# nola7a.net
KiCad netlist of a schematic drawn in EAGLE
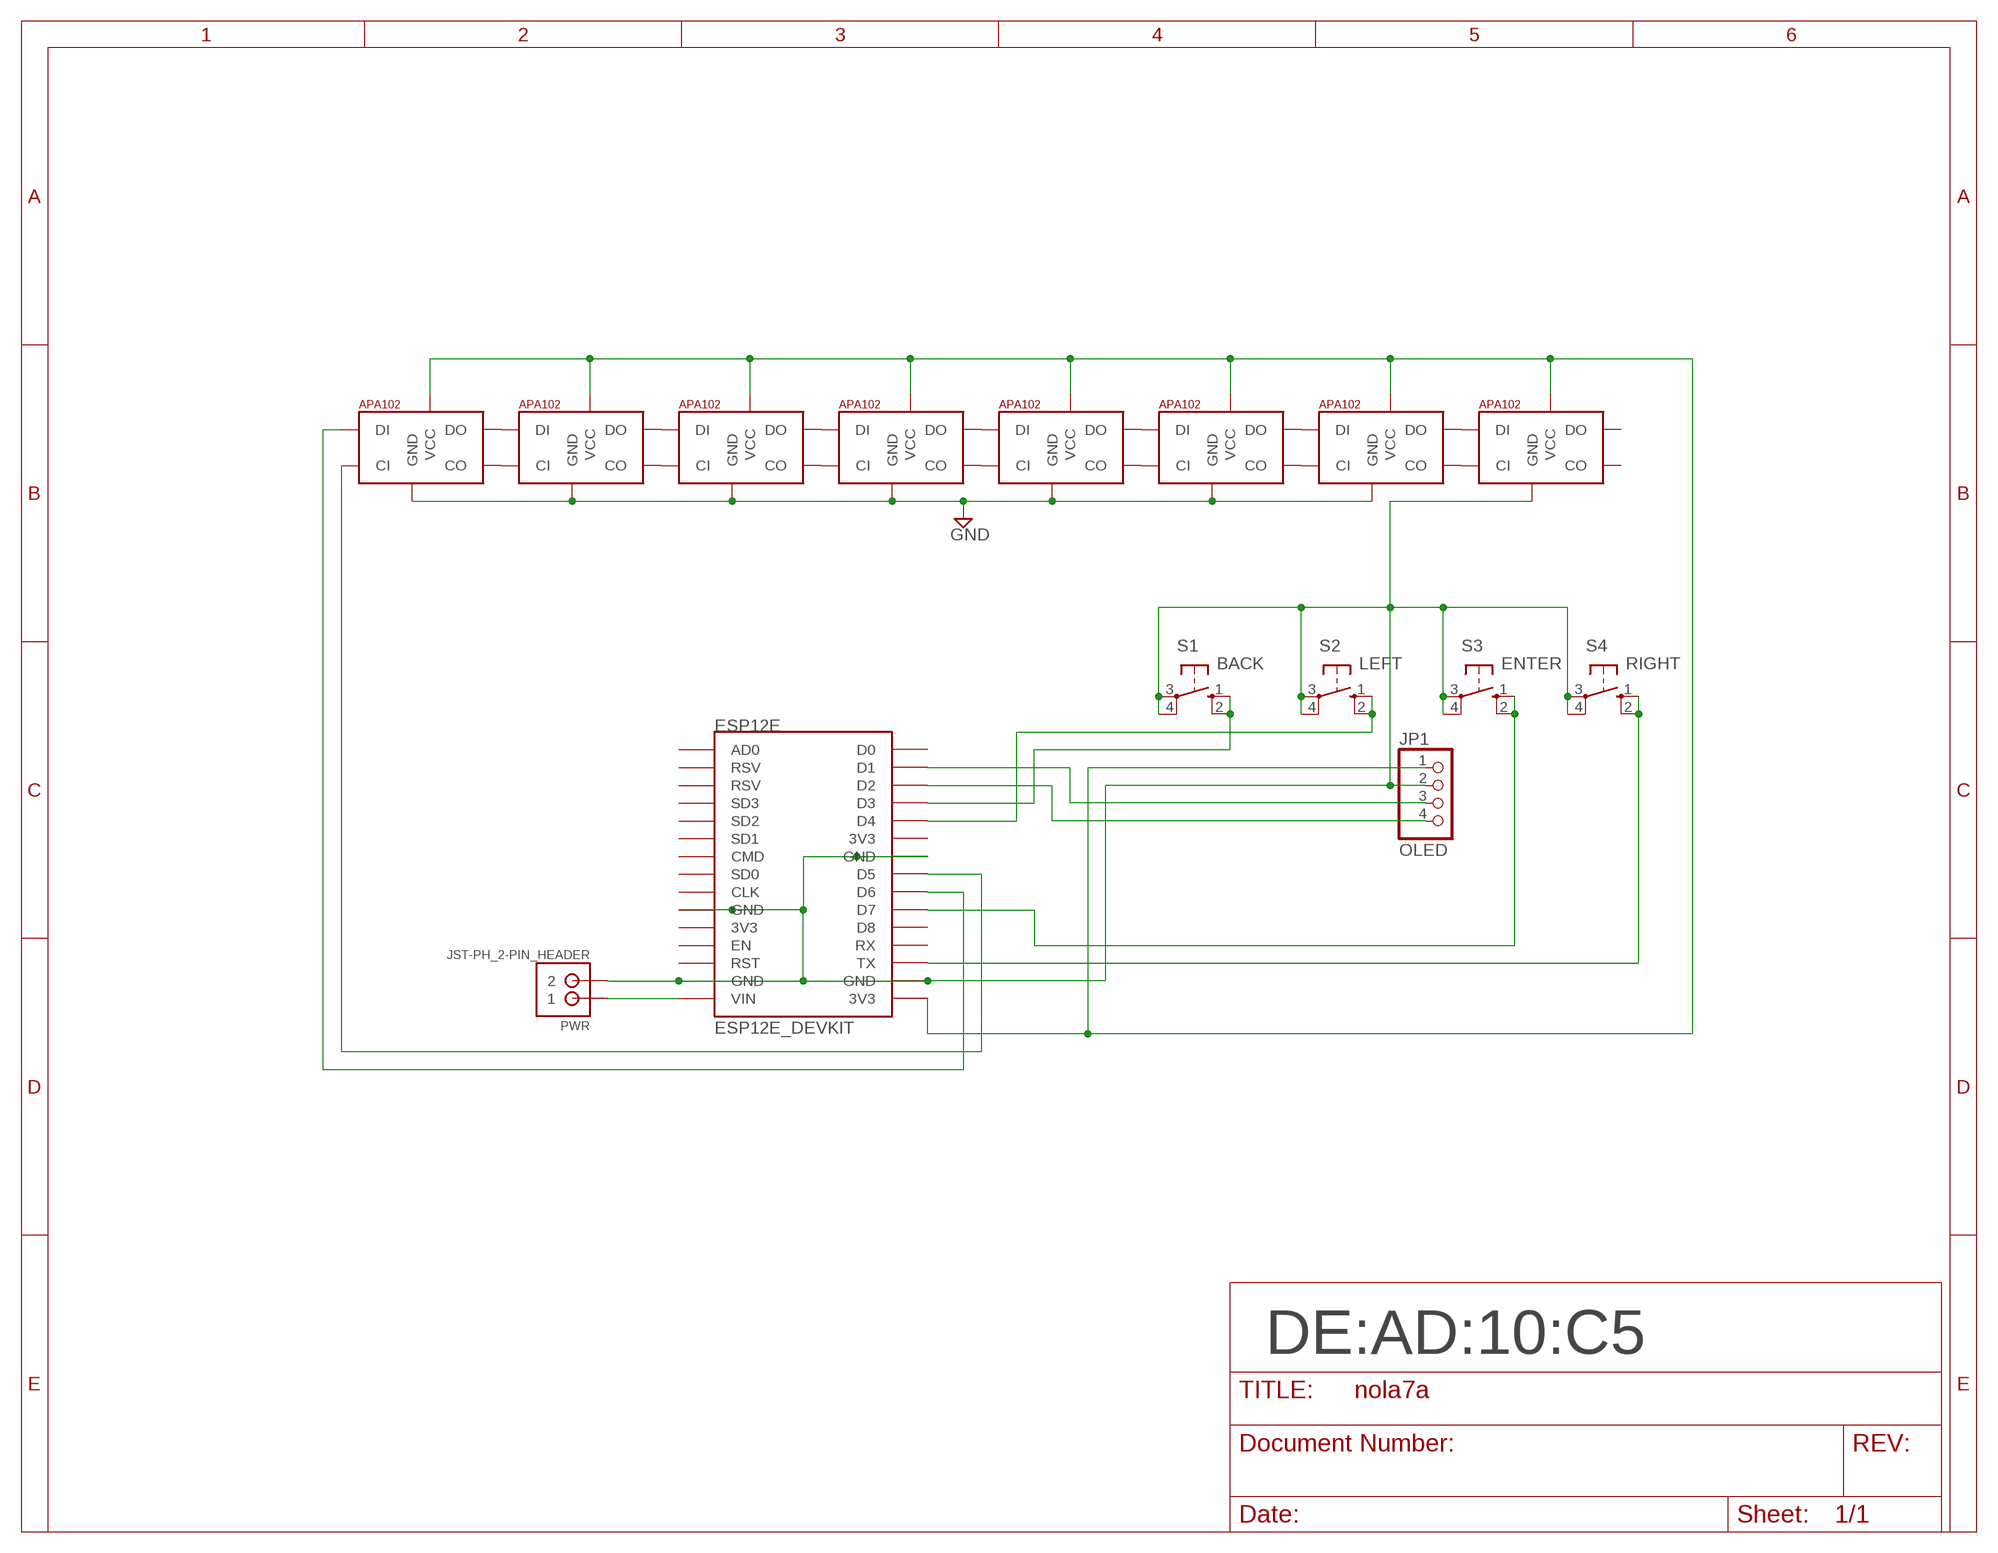
[diagram p0: schematic, sheet 1]

(export (version "E")
  (design (tool "Eeschema 10.0.6"))
  (components
    (comp (ref "ESP12E")
      (value "ESP12E_DEVKIT")
      (footprint "eagle-import:ESP12E_DEVKIT")
      (libsource (lib "eagle-import") (part "ESP12E_DEVKIT"))
    )
    (comp (ref "JP1")
      (value "OLED")
      (footprint "eagle-import:1X04")
      (libsource (lib "eagle-import") (part "PINHD-1X4"))
    )
    (comp (ref "LED1")
      (value "APA1025050")
      (footprint "eagle-import:APA102_5050")
      (libsource (lib "eagle-import") (part "APA1025050"))
    )
    (comp (ref "LED2")
      (value "APA1025050")
      (footprint "eagle-import:APA102_5050")
      (libsource (lib "eagle-import") (part "APA1025050"))
    )
    (comp (ref "LED3")
      (value "APA1025050")
      (footprint "eagle-import:APA102_5050")
      (libsource (lib "eagle-import") (part "APA1025050"))
    )
    (comp (ref "LED4")
      (value "APA1025050")
      (footprint "eagle-import:APA102_5050")
      (libsource (lib "eagle-import") (part "APA1025050"))
    )
    (comp (ref "LED5")
      (value "APA1025050")
      (footprint "eagle-import:APA102_5050")
      (libsource (lib "eagle-import") (part "APA1025050"))
    )
    (comp (ref "LED6")
      (value "APA1025050")
      (footprint "eagle-import:APA102_5050")
      (libsource (lib "eagle-import") (part "APA1025050"))
    )
    (comp (ref "LED7")
      (value "APA1025050")
      (footprint "eagle-import:APA102_5050")
      (libsource (lib "eagle-import") (part "APA1025050"))
    )
    (comp (ref "LED8")
      (value "APA1025050")
      (footprint "eagle-import:APA102_5050")
      (libsource (lib "eagle-import") (part "APA1025050"))
    )
    (comp (ref "PWR")
      (value "JST-PH_2-PIN_HEADER")
      (footprint "eagle-import:JST_B2B-PH_HEADER")
      (libsource (lib "eagle-import") (part "JST-PH_2-PIN_HEADER"))
    )
    (comp (ref "S1")
      (value "BACK")
      (footprint "eagle-import:B3F-10XX")
      (fields (field (name "MPN") "B3F-1000"))
      (libsource (lib "eagle-import") (part "10-XX"))
    )
    (comp (ref "S2")
      (value "LEFT")
      (footprint "eagle-import:B3F-10XX")
      (fields (field (name "MPN") "B3F-1000"))
      (libsource (lib "eagle-import") (part "10-XX"))
    )
    (comp (ref "S3")
      (value "ENTER")
      (footprint "eagle-import:B3F-10XX")
      (fields (field (name "MPN") "B3F-1000"))
      (libsource (lib "eagle-import") (part "10-XX"))
    )
    (comp (ref "S4")
      (value "RIGHT")
      (footprint "eagle-import:B3F-10XX")
      (fields (field (name "MPN") "B3F-1000"))
      (libsource (lib "eagle-import") (part "10-XX"))
    )
  )
  (nets
    (net (code "1") (name "GND") (class "Default")
      (node (ref "ESP12E") (pin "GND@0") (pinfunction "GND_GND@0") (pintype "bidirectional"))
      (node (ref "ESP12E") (pin "GND@1") (pinfunction "GND_GND@1") (pintype "bidirectional"))
      (node (ref "ESP12E") (pin "GND@2") (pinfunction "GND_GND@2") (pintype "bidirectional"))
      (node (ref "ESP12E") (pin "GND@3") (pinfunction "GND_GND@3") (pintype "bidirectional"))
      (node (ref "JP1") (pin "2") (pinfunction "2_2") (pintype "passive"))
      (node (ref "LED1") (pin "6") (pinfunction "GND_6") (pintype "bidirectional"))
      (node (ref "LED2") (pin "6") (pinfunction "GND_6") (pintype "bidirectional"))
      (node (ref "LED3") (pin "6") (pinfunction "GND_6") (pintype "bidirectional"))
      (node (ref "LED4") (pin "6") (pinfunction "GND_6") (pintype "bidirectional"))
      (node (ref "LED5") (pin "6") (pinfunction "GND_6") (pintype "bidirectional"))
      (node (ref "LED6") (pin "6") (pinfunction "GND_6") (pintype "bidirectional"))
      (node (ref "LED7") (pin "6") (pinfunction "GND_6") (pintype "bidirectional"))
      (node (ref "LED8") (pin "6") (pinfunction "GND_6") (pintype "bidirectional"))
      (node (ref "PWR") (pin "P2") (pinfunction "2_P2") (pintype "bidirectional"))
      (node (ref "S1") (pin "3") (pinfunction "P_3") (pintype "passive"))
      (node (ref "S1") (pin "4") (pinfunction "P1_4") (pintype "passive"))
      (node (ref "S2") (pin "3") (pinfunction "P_3") (pintype "passive"))
      (node (ref "S2") (pin "4") (pinfunction "P1_4") (pintype "passive"))
      (node (ref "S3") (pin "3") (pinfunction "P_3") (pintype "passive"))
      (node (ref "S3") (pin "4") (pinfunction "P1_4") (pintype "passive"))
      (node (ref "S4") (pin "3") (pinfunction "P_3") (pintype "passive"))
      (node (ref "S4") (pin "4") (pinfunction "P1_4") (pintype "passive"))
    )
    (net (code "2") (name "Net-(ESP12E-PadD1)") (class "Default")
      (node (ref "ESP12E") (pin "D1") (pinfunction "D1_D1") (pintype "bidirectional"))
      (node (ref "JP1") (pin "3") (pinfunction "3_3") (pintype "passive"))
    )
    (net (code "3") (name "Net-(ESP12E-PadD2)") (class "Default")
      (node (ref "ESP12E") (pin "D2") (pinfunction "D2_D2") (pintype "bidirectional"))
      (node (ref "JP1") (pin "4") (pinfunction "4_4") (pintype "passive"))
    )
    (net (code "4") (name "Net-(LED1-CI)") (class "Default")
      (node (ref "ESP12E") (pin "D5") (pinfunction "D5_D5") (pintype "bidirectional"))
      (node (ref "LED1") (pin "5") (pinfunction "CI_5") (pintype "bidirectional"))
    )
    (net (code "5") (name "Net-(LED1-CO)") (class "Default")
      (node (ref "LED1") (pin "2") (pinfunction "CO_2") (pintype "bidirectional"))
      (node (ref "LED2") (pin "5") (pinfunction "CI_5") (pintype "bidirectional"))
    )
    (net (code "6") (name "Net-(LED1-DI)") (class "Default")
      (node (ref "ESP12E") (pin "D6") (pinfunction "D6_D6") (pintype "bidirectional"))
      (node (ref "LED1") (pin "4") (pinfunction "DI_4") (pintype "bidirectional"))
    )
    (net (code "7") (name "Net-(LED1-DO)") (class "Default")
      (node (ref "LED1") (pin "3") (pinfunction "DO_3") (pintype "bidirectional"))
      (node (ref "LED2") (pin "4") (pinfunction "DI_4") (pintype "bidirectional"))
    )
    (net (code "8") (name "Net-(LED1-VCC)") (class "Default")
      (node (ref "ESP12E") (pin "3V3@2") (pinfunction "3V3_3V3@2") (pintype "bidirectional"))
      (node (ref "JP1") (pin "1") (pinfunction "1_1") (pintype "passive"))
      (node (ref "LED1") (pin "1") (pinfunction "VCC_1") (pintype "bidirectional"))
      (node (ref "LED2") (pin "1") (pinfunction "VCC_1") (pintype "bidirectional"))
      (node (ref "LED3") (pin "1") (pinfunction "VCC_1") (pintype "bidirectional"))
      (node (ref "LED4") (pin "1") (pinfunction "VCC_1") (pintype "bidirectional"))
      (node (ref "LED5") (pin "1") (pinfunction "VCC_1") (pintype "bidirectional"))
      (node (ref "LED6") (pin "1") (pinfunction "VCC_1") (pintype "bidirectional"))
      (node (ref "LED7") (pin "1") (pinfunction "VCC_1") (pintype "bidirectional"))
      (node (ref "LED8") (pin "1") (pinfunction "VCC_1") (pintype "bidirectional"))
    )
    (net (code "9") (name "Net-(LED2-CO)") (class "Default")
      (node (ref "LED2") (pin "2") (pinfunction "CO_2") (pintype "bidirectional"))
      (node (ref "LED3") (pin "5") (pinfunction "CI_5") (pintype "bidirectional"))
    )
    (net (code "10") (name "Net-(LED2-DO)") (class "Default")
      (node (ref "LED2") (pin "3") (pinfunction "DO_3") (pintype "bidirectional"))
      (node (ref "LED3") (pin "4") (pinfunction "DI_4") (pintype "bidirectional"))
    )
    (net (code "11") (name "Net-(LED3-CO)") (class "Default")
      (node (ref "LED3") (pin "2") (pinfunction "CO_2") (pintype "bidirectional"))
      (node (ref "LED4") (pin "5") (pinfunction "CI_5") (pintype "bidirectional"))
    )
    (net (code "12") (name "Net-(LED3-DO)") (class "Default")
      (node (ref "LED3") (pin "3") (pinfunction "DO_3") (pintype "bidirectional"))
      (node (ref "LED4") (pin "4") (pinfunction "DI_4") (pintype "bidirectional"))
    )
    (net (code "13") (name "Net-(LED4-CO)") (class "Default")
      (node (ref "LED4") (pin "2") (pinfunction "CO_2") (pintype "bidirectional"))
      (node (ref "LED5") (pin "5") (pinfunction "CI_5") (pintype "bidirectional"))
    )
    (net (code "14") (name "Net-(LED4-DO)") (class "Default")
      (node (ref "LED4") (pin "3") (pinfunction "DO_3") (pintype "bidirectional"))
      (node (ref "LED5") (pin "4") (pinfunction "DI_4") (pintype "bidirectional"))
    )
    (net (code "15") (name "Net-(LED5-CO)") (class "Default")
      (node (ref "LED5") (pin "2") (pinfunction "CO_2") (pintype "bidirectional"))
      (node (ref "LED6") (pin "5") (pinfunction "CI_5") (pintype "bidirectional"))
    )
    (net (code "16") (name "Net-(LED5-DO)") (class "Default")
      (node (ref "LED5") (pin "3") (pinfunction "DO_3") (pintype "bidirectional"))
      (node (ref "LED6") (pin "4") (pinfunction "DI_4") (pintype "bidirectional"))
    )
    (net (code "17") (name "Net-(LED6-CO)") (class "Default")
      (node (ref "LED6") (pin "2") (pinfunction "CO_2") (pintype "bidirectional"))
      (node (ref "LED7") (pin "5") (pinfunction "CI_5") (pintype "bidirectional"))
    )
    (net (code "18") (name "Net-(LED6-DO)") (class "Default")
      (node (ref "LED6") (pin "3") (pinfunction "DO_3") (pintype "bidirectional"))
      (node (ref "LED7") (pin "4") (pinfunction "DI_4") (pintype "bidirectional"))
    )
    (net (code "19") (name "Net-(LED7-CO)") (class "Default")
      (node (ref "LED7") (pin "2") (pinfunction "CO_2") (pintype "bidirectional"))
      (node (ref "LED8") (pin "5") (pinfunction "CI_5") (pintype "bidirectional"))
    )
    (net (code "20") (name "Net-(LED7-DO)") (class "Default")
      (node (ref "LED7") (pin "3") (pinfunction "DO_3") (pintype "bidirectional"))
      (node (ref "LED8") (pin "4") (pinfunction "DI_4") (pintype "bidirectional"))
    )
    (net (code "21") (name "Net-(PWR-1)") (class "Default")
      (node (ref "ESP12E") (pin "VIN") (pinfunction "VIN_VIN") (pintype "bidirectional"))
      (node (ref "PWR") (pin "P1") (pinfunction "1_P1") (pintype "bidirectional"))
    )
    (net (code "22") (name "Net-(S1-S)") (class "Default")
      (node (ref "ESP12E") (pin "D3") (pinfunction "D3_D3") (pintype "bidirectional"))
      (node (ref "S1") (pin "1") (pinfunction "S_1") (pintype "passive"))
      (node (ref "S1") (pin "2") (pinfunction "S1_2") (pintype "passive"))
    )
    (net (code "23") (name "Net-(S2-S)") (class "Default")
      (node (ref "ESP12E") (pin "D4") (pinfunction "D4_D4") (pintype "bidirectional"))
      (node (ref "S2") (pin "1") (pinfunction "S_1") (pintype "passive"))
      (node (ref "S2") (pin "2") (pinfunction "S1_2") (pintype "passive"))
    )
    (net (code "24") (name "Net-(S3-S)") (class "Default")
      (node (ref "ESP12E") (pin "D7") (pinfunction "D7_D7") (pintype "bidirectional"))
      (node (ref "S3") (pin "1") (pinfunction "S_1") (pintype "passive"))
      (node (ref "S3") (pin "2") (pinfunction "S1_2") (pintype "passive"))
    )
    (net (code "25") (name "Net-(S4-S)") (class "Default")
      (node (ref "ESP12E") (pin "TX") (pinfunction "TX_TX") (pintype "bidirectional"))
      (node (ref "S4") (pin "1") (pinfunction "S_1") (pintype "passive"))
      (node (ref "S4") (pin "2") (pinfunction "S1_2") (pintype "passive"))
    )
    (net (code "26") (name "unconnected-(ESP12E-3V3-Pad3V3@0)") (class "Default")
      (node (ref "ESP12E") (pin "3V3@0") (pinfunction "3V3_3V3@0") (pintype "bidirectional"))
    )
    (net (code "27") (name "unconnected-(ESP12E-3V3-Pad3V3@1)") (class "Default")
      (node (ref "ESP12E") (pin "3V3@1") (pinfunction "3V3_3V3@1") (pintype "bidirectional"))
    )
    (net (code "28") (name "unconnected-(ESP12E-PadAD0)") (class "Default")
      (node (ref "ESP12E") (pin "AD0") (pinfunction "AD0_AD0") (pintype "bidirectional"))
    )
    (net (code "29") (name "unconnected-(ESP12E-PadCLK)") (class "Default")
      (node (ref "ESP12E") (pin "CLK") (pinfunction "CLK_CLK") (pintype "bidirectional"))
    )
    (net (code "30") (name "unconnected-(ESP12E-PadCMD)") (class "Default")
      (node (ref "ESP12E") (pin "CMD") (pinfunction "CMD_CMD") (pintype "bidirectional"))
    )
    (net (code "31") (name "unconnected-(ESP12E-PadD0)") (class "Default")
      (node (ref "ESP12E") (pin "D0") (pinfunction "D0_D0") (pintype "bidirectional"))
    )
    (net (code "32") (name "unconnected-(ESP12E-PadD8)") (class "Default")
      (node (ref "ESP12E") (pin "D8") (pinfunction "D8_D8") (pintype "bidirectional"))
    )
    (net (code "33") (name "unconnected-(ESP12E-PadEN)") (class "Default")
      (node (ref "ESP12E") (pin "EN") (pinfunction "EN_EN") (pintype "bidirectional"))
    )
    (net (code "34") (name "unconnected-(ESP12E-PadRST)") (class "Default")
      (node (ref "ESP12E") (pin "RST") (pinfunction "RST_RST") (pintype "bidirectional"))
    )
    (net (code "35") (name "unconnected-(ESP12E-PadRX)") (class "Default")
      (node (ref "ESP12E") (pin "RX") (pinfunction "RX_RX") (pintype "bidirectional"))
    )
    (net (code "36") (name "unconnected-(ESP12E-PadSD0)") (class "Default")
      (node (ref "ESP12E") (pin "SD0") (pinfunction "SD0_SD0") (pintype "bidirectional"))
    )
    (net (code "37") (name "unconnected-(ESP12E-PadSD1)") (class "Default")
      (node (ref "ESP12E") (pin "SD1") (pinfunction "SD1_SD1") (pintype "bidirectional"))
    )
    (net (code "38") (name "unconnected-(ESP12E-PadSD2)") (class "Default")
      (node (ref "ESP12E") (pin "SD2") (pinfunction "SD2_SD2") (pintype "bidirectional"))
    )
    (net (code "39") (name "unconnected-(ESP12E-PadSD3)") (class "Default")
      (node (ref "ESP12E") (pin "SD3") (pinfunction "SD3_SD3") (pintype "bidirectional"))
    )
    (net (code "40") (name "unconnected-(ESP12E-RSV-PadRSV@0)") (class "Default")
      (node (ref "ESP12E") (pin "RSV@0") (pinfunction "RSV_RSV@0") (pintype "bidirectional"))
    )
    (net (code "41") (name "unconnected-(ESP12E-RSV-PadRSV@1)") (class "Default")
      (node (ref "ESP12E") (pin "RSV@1") (pinfunction "RSV_RSV@1") (pintype "bidirectional"))
    )
    (net (code "42") (name "unconnected-(LED8-CO-Pad2)") (class "Default")
      (node (ref "LED8") (pin "2") (pinfunction "CO_2") (pintype "bidirectional"))
    )
    (net (code "43") (name "unconnected-(LED8-DO-Pad3)") (class "Default")
      (node (ref "LED8") (pin "3") (pinfunction "DO_3") (pintype "bidirectional"))
    )
  )
)
